# Bus.net
KiCad netlist of a schematic drawn in Altium Designer
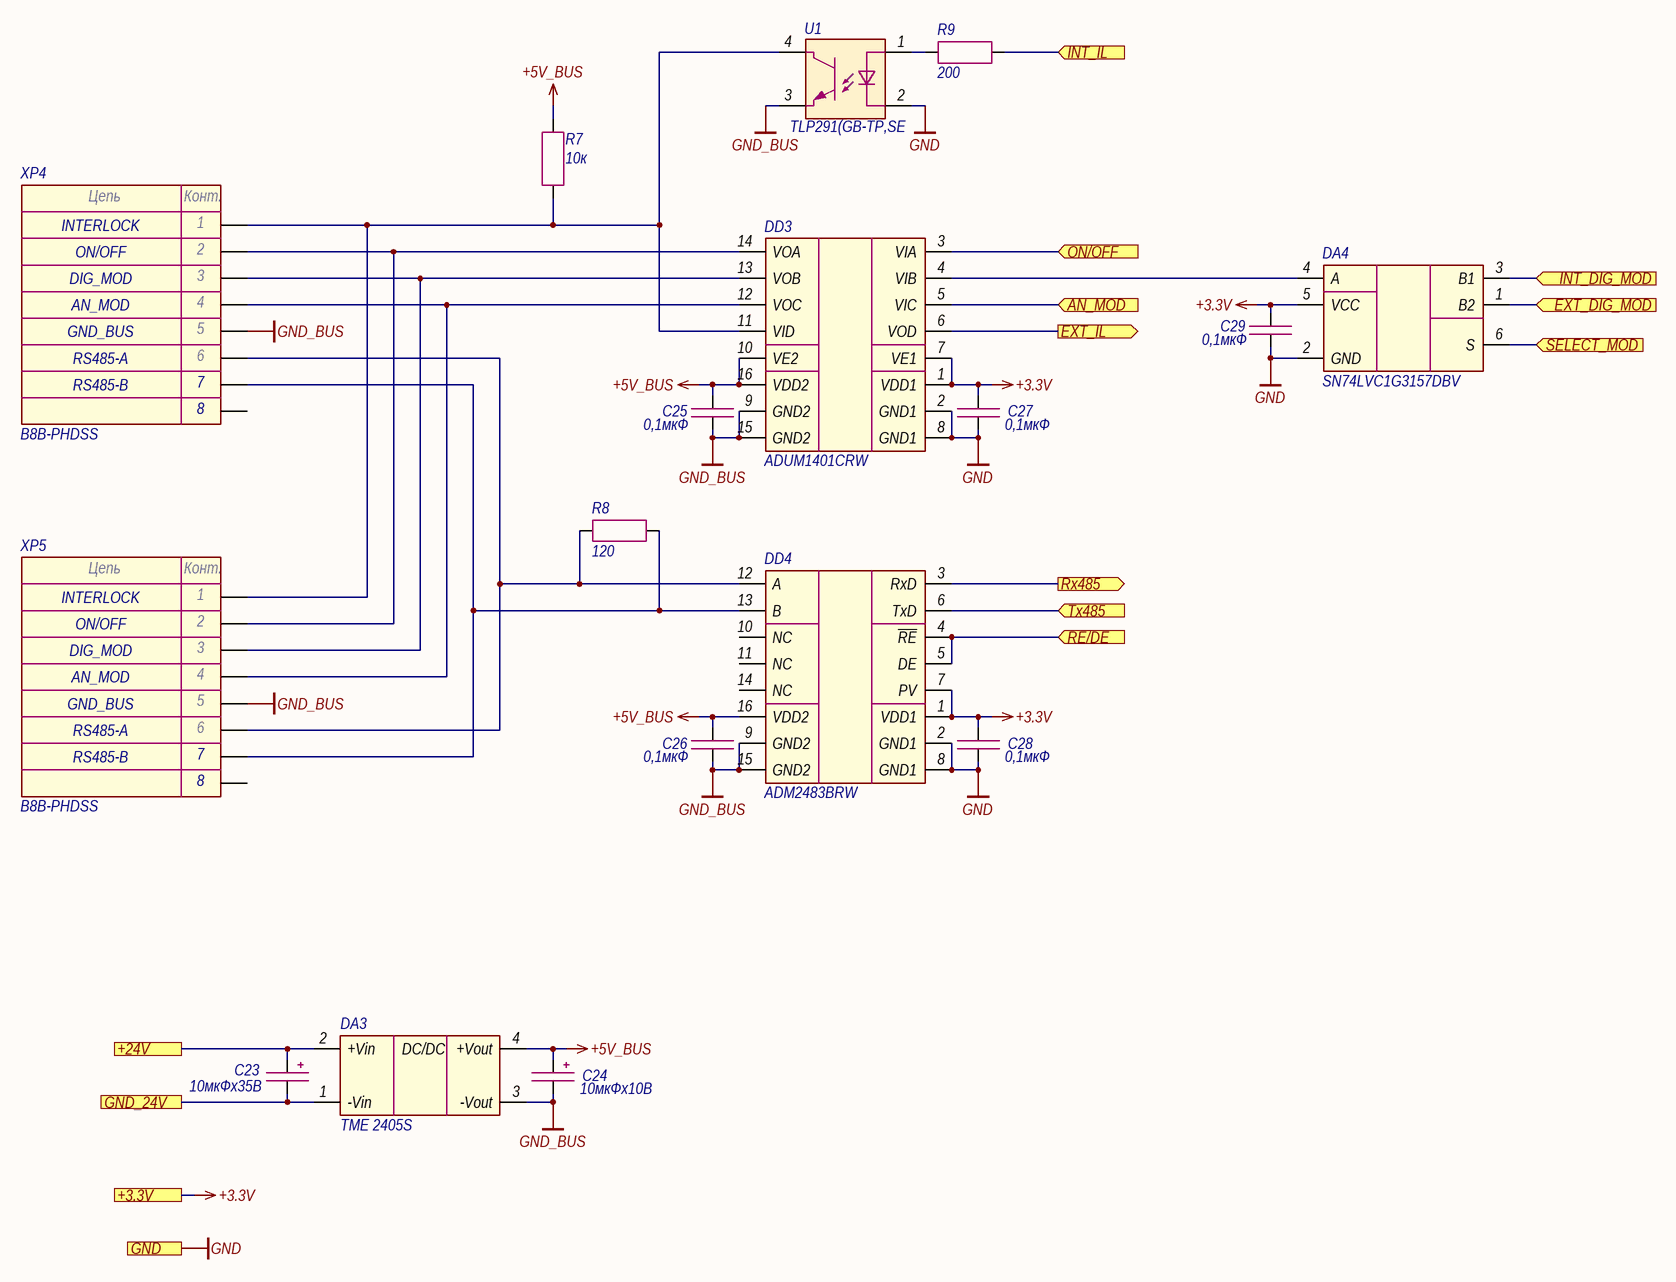
[diagram p0: Bus.SchDoc]

(export (version "E")
  (design (tool "Eeschema 10.0.6"))
  (components
    (comp (ref "C23")
      (value "10мкФх35B")
      (footprint "Pcb_library:CAP_C")
      (libsource (lib "Schem_library") (part "Capacitor_Polar"))
    )
    (comp (ref "C24")
      (value "10мкФх10B")
      (footprint "Pcb_library:CAP_A")
      (libsource (lib "Schem_library") (part "Capacitor_Polar"))
    )
    (comp (ref "C25")
      (value "0,1мкФ")
      (footprint "Pcb_library:CAP_0603")
      (fields (field (name "MANUFACTURER") "Murata"))
      (libsource (lib "Schem_library") (part "Capacitor"))
    )
    (comp (ref "C26")
      (value "0,1мкФ")
      (footprint "Pcb_library:CAP_0603")
      (fields (field (name "MANUFACTURER") "Murata"))
      (libsource (lib "Schem_library") (part "Capacitor"))
    )
    (comp (ref "C27")
      (value "0,1мкФ")
      (footprint "Pcb_library:CAP_0603")
      (fields (field (name "MANUFACTURER") "Murata"))
      (libsource (lib "Schem_library") (part "Capacitor"))
    )
    (comp (ref "C28")
      (value "0,1мкФ")
      (footprint "Pcb_library:CAP_0603")
      (fields (field (name "MANUFACTURER") "Murata"))
      (libsource (lib "Schem_library") (part "Capacitor"))
    )
    (comp (ref "C29")
      (value "0,1мкФ")
      (footprint "Pcb_library:CAP_0603")
      (fields (field (name "MANUFACTURER") "Murata"))
      (libsource (lib "Schem_library") (part "Capacitor"))
    )
    (comp (ref "DA3")
      (value "TME 2405S")
      (footprint "Pcb_library:TME (SIP-4)")
      (fields (field (name "MANUFACTURER") "Traco Power"))
      (libsource (lib "Schem_library") (part "TME"))
    )
    (comp (ref "DA4")
      (value "SN74LVC1G3157DBV")
      (footprint "Pcb_library:SOT-23-6")
      (fields (field (name "MANUFACTURER") "Texas Instruments"))
      (libsource (lib "Schem_library") (part "SN74LVC1G3157"))
    )
    (comp (ref "DD3")
      (value "ADUM1401CRW")
      (footprint "Pcb_library:SOIC-16W")
      (fields (field (name "MANUFACTURER") "Analog Devices"))
      (libsource (lib "Schem_library") (part "ADUM1401"))
    )
    (comp (ref "DD4")
      (value "ADM2483BRW")
      (footprint "Pcb_library:SOIC-16W")
      (fields (field (name "MANUFACTURER") "Analog Devices"))
      (libsource (lib "Schem_library") (part "ADM2483BRW"))
    )
    (comp (ref "R7")
      (value "10к")
      (footprint "Pcb_library:RES_0603")
      (fields (field (name "MANUFACTURER") "Yageo"))
      (libsource (lib "Schem_library") (part "Resistor"))
    )
    (comp (ref "R8")
      (value "120")
      (footprint "Pcb_library:RES_0805")
      (fields (field (name "MANUFACTURER") "Yageo"))
      (libsource (lib "Schem_library") (part "Resistor"))
    )
    (comp (ref "R9")
      (value "200")
      (footprint "Pcb_library:RES_0603")
      (fields (field (name "MANUFACTURER") "Yageo"))
      (libsource (lib "Schem_library") (part "Resistor"))
    )
    (comp (ref "U1")
      (value "TLP291(GB-TP,SE")
      (footprint "Pcb_library:11-3C1")
      (fields (field (name "MANUFACTURER") "Toshiba"))
      (libsource (lib "Schem_library") (part "TLP291"))
    )
    (comp (ref "XP4")
      (value "B8B-PHDSS")
      (footprint "Pcb_library:B8B-PHDSS")
      (fields (field (name "MANUFACTURER") "JST"))
      (libsource (lib "Schem_library") (part "Connector-8"))
    )
    (comp (ref "XP5")
      (value "B8B-PHDSS")
      (footprint "Pcb_library:B8B-PHDSS")
      (fields (field (name "MANUFACTURER") "JST"))
      (libsource (lib "Schem_library") (part "Connector-8"))
    )
  )
  (nets
    (net (code "1") (name "+3.3V") (class "Default")
      (node (ref "C27") (pin "1") (pinfunction "1_1") (pintype "passive"))
      (node (ref "C28") (pin "1") (pinfunction "1_1") (pintype "passive"))
      (node (ref "C29") (pin "1") (pinfunction "1_1") (pintype "passive"))
      (node (ref "DA4") (pin "5") (pinfunction "VCC_5") (pintype "passive"))
      (node (ref "DD3") (pin "1") (pinfunction "VDD1_1") (pintype "passive"))
      (node (ref "DD3") (pin "7") (pinfunction "VE1_7") (pintype "passive"))
      (node (ref "DD4") (pin "1") (pinfunction "VDD1_1") (pintype "passive"))
      (node (ref "DD4") (pin "7") (pinfunction "PV_7") (pintype "passive"))
    )
    (net (code "2") (name "+5V_BUS") (class "Default")
      (node (ref "C24") (pin "1") (pinfunction "1_1") (pintype "passive"))
      (node (ref "C25") (pin "1") (pinfunction "1_1") (pintype "passive"))
      (node (ref "C26") (pin "1") (pinfunction "1_1") (pintype "passive"))
      (node (ref "DA3") (pin "4") (pinfunction "+Vout_4") (pintype "passive"))
      (node (ref "DD3") (pin "10") (pinfunction "VE2_10") (pintype "passive"))
      (node (ref "DD3") (pin "16") (pinfunction "VDD2_16") (pintype "passive"))
      (node (ref "DD4") (pin "16") (pinfunction "VDD2_16") (pintype "passive"))
      (node (ref "R7") (pin "1") (pinfunction "1_1") (pintype "passive"))
    )
    (net (code "3") (name "/+24V") (class "Default")
      (node (ref "C23") (pin "1") (pinfunction "1_1") (pintype "passive"))
      (node (ref "DA3") (pin "2") (pinfunction "+Vin_2") (pintype "passive"))
    )
    (net (code "4") (name "/AN_MOD") (class "Default")
      (node (ref "DD3") (pin "5") (pinfunction "VIC_5") (pintype "passive"))
    )
    (net (code "5") (name "/EXT_DIG_MOD") (class "Default")
      (node (ref "DA4") (pin "1") (pinfunction "B2_1") (pintype "passive"))
    )
    (net (code "6") (name "/EXT_IL") (class "Default")
      (node (ref "DD3") (pin "6") (pinfunction "VOD_6") (pintype "passive"))
    )
    (net (code "7") (name "/GND_24V") (class "Default")
      (node (ref "C23") (pin "2") (pinfunction "2_2") (pintype "passive"))
      (node (ref "DA3") (pin "1") (pinfunction "-Vin_1") (pintype "passive"))
    )
    (net (code "8") (name "/INT_DIG_MOD") (class "Default")
      (node (ref "DA4") (pin "3") (pinfunction "B1_3") (pintype "passive"))
    )
    (net (code "9") (name "/INT_IL") (class "Default")
      (node (ref "R9") (pin "1") (pinfunction "1_1") (pintype "passive"))
    )
    (net (code "10") (name "/ON{slash}OFF") (class "Default")
      (node (ref "DD3") (pin "3") (pinfunction "VIA_3") (pintype "passive"))
    )
    (net (code "11") (name "/RE{slash}DE") (class "Default")
      (node (ref "DD4") (pin "4") (pinfunction "~{RE}_4") (pintype "passive"))
      (node (ref "DD4") (pin "5") (pinfunction "DE_5") (pintype "passive"))
    )
    (net (code "12") (name "/Rx485") (class "Default")
      (node (ref "DD4") (pin "3") (pinfunction "RxD_3") (pintype "passive"))
    )
    (net (code "13") (name "/SELECT_MOD") (class "Default")
      (node (ref "DA4") (pin "6") (pinfunction "S_6") (pintype "passive"))
    )
    (net (code "14") (name "/Tx485") (class "Default")
      (node (ref "DD4") (pin "6") (pinfunction "TxD_6") (pintype "passive"))
    )
    (net (code "15") (name "GND") (class "Default")
      (node (ref "C27") (pin "2") (pinfunction "2_2") (pintype "passive"))
      (node (ref "C28") (pin "2") (pinfunction "2_2") (pintype "passive"))
      (node (ref "C29") (pin "2") (pinfunction "2_2") (pintype "passive"))
      (node (ref "DA4") (pin "2") (pinfunction "GND_2") (pintype "passive"))
      (node (ref "DD3") (pin "2") (pinfunction "GND1_2") (pintype "passive"))
      (node (ref "DD3") (pin "8") (pinfunction "GND1_8") (pintype "passive"))
      (node (ref "DD4") (pin "2") (pinfunction "GND1_2") (pintype "passive"))
      (node (ref "DD4") (pin "8") (pinfunction "GND1_8") (pintype "passive"))
      (node (ref "U1") (pin "2") (pintype "passive"))
    )
    (net (code "16") (name "GND_BUS") (class "Default")
      (node (ref "C24") (pin "2") (pinfunction "2_2") (pintype "passive"))
      (node (ref "C25") (pin "2") (pinfunction "2_2") (pintype "passive"))
      (node (ref "C26") (pin "2") (pinfunction "2_2") (pintype "passive"))
      (node (ref "DA3") (pin "3") (pinfunction "-Vout_3") (pintype "passive"))
      (node (ref "DD3") (pin "15") (pinfunction "GND2_15") (pintype "passive"))
      (node (ref "DD3") (pin "9") (pinfunction "GND2_9") (pintype "passive"))
      (node (ref "DD4") (pin "15") (pinfunction "GND2_15") (pintype "passive"))
      (node (ref "DD4") (pin "9") (pinfunction "GND2_9") (pintype "passive"))
      (node (ref "U1") (pin "3") (pintype "passive"))
      (node (ref "XP4") (pin "5") (pintype "passive"))
      (node (ref "XP5") (pin "5") (pintype "passive"))
    )
    (net (code "17") (name "Net-(DA4-A)") (class "Default")
      (node (ref "DA4") (pin "4") (pinfunction "A_4") (pintype "passive"))
      (node (ref "DD3") (pin "4") (pinfunction "VIB_4") (pintype "passive"))
    )
    (net (code "18") (name "Net-(DD3-VID)") (class "Default")
      (node (ref "DD3") (pin "11") (pinfunction "VID_11") (pintype "passive"))
      (node (ref "R7") (pin "2") (pinfunction "2_2") (pintype "passive"))
      (node (ref "U1") (pin "4") (pintype "passive"))
      (node (ref "XP4") (pin "1") (pintype "passive"))
      (node (ref "XP5") (pin "1") (pintype "passive"))
    )
    (net (code "19") (name "Net-(DD3-VOA)") (class "Default")
      (node (ref "DD3") (pin "14") (pinfunction "VOA_14") (pintype "passive"))
      (node (ref "XP4") (pin "2") (pintype "passive"))
      (node (ref "XP5") (pin "2") (pintype "passive"))
    )
    (net (code "20") (name "Net-(DD3-VOB)") (class "Default")
      (node (ref "DD3") (pin "13") (pinfunction "VOB_13") (pintype "passive"))
      (node (ref "XP4") (pin "3") (pintype "passive"))
      (node (ref "XP5") (pin "3") (pintype "passive"))
    )
    (net (code "21") (name "Net-(DD3-VOC)") (class "Default")
      (node (ref "DD3") (pin "12") (pinfunction "VOC_12") (pintype "passive"))
      (node (ref "XP4") (pin "4") (pintype "passive"))
      (node (ref "XP5") (pin "4") (pintype "passive"))
    )
    (net (code "22") (name "Net-(DD4-A)") (class "Default")
      (node (ref "DD4") (pin "12") (pinfunction "A_12") (pintype "passive"))
      (node (ref "R8") (pin "1") (pinfunction "1_1") (pintype "passive"))
      (node (ref "XP4") (pin "6") (pintype "passive"))
      (node (ref "XP5") (pin "6") (pintype "passive"))
    )
    (net (code "23") (name "Net-(DD4-B)") (class "Default")
      (node (ref "DD4") (pin "13") (pinfunction "B_13") (pintype "passive"))
      (node (ref "R8") (pin "2") (pinfunction "2_2") (pintype "passive"))
      (node (ref "XP4") (pin "7") (pintype "passive"))
      (node (ref "XP5") (pin "7") (pintype "passive"))
    )
    (net (code "24") (name "Net-(R9-Pad2)") (class "Default")
      (node (ref "R9") (pin "2") (pinfunction "2_2") (pintype "passive"))
      (node (ref "U1") (pin "1") (pintype "passive"))
    )
    (net (code "25") (name "unconnected-(DD4-NC-Pad10)") (class "Default")
      (node (ref "DD4") (pin "10") (pinfunction "NC_10") (pintype "passive"))
    )
    (net (code "26") (name "unconnected-(DD4-NC-Pad11)") (class "Default")
      (node (ref "DD4") (pin "11") (pinfunction "NC_11") (pintype "passive"))
    )
    (net (code "27") (name "unconnected-(DD4-NC-Pad14)") (class "Default")
      (node (ref "DD4") (pin "14") (pinfunction "NC_14") (pintype "passive"))
    )
    (net (code "28") (name "unconnected-(XP4-Pad8)") (class "Default")
      (node (ref "XP4") (pin "8") (pintype "passive"))
    )
    (net (code "29") (name "unconnected-(XP5-Pad8)") (class "Default")
      (node (ref "XP5") (pin "8") (pintype "passive"))
    )
  )
)
